# NBIOT.net
KiCad netlist of a schematic drawn in Altium Designer
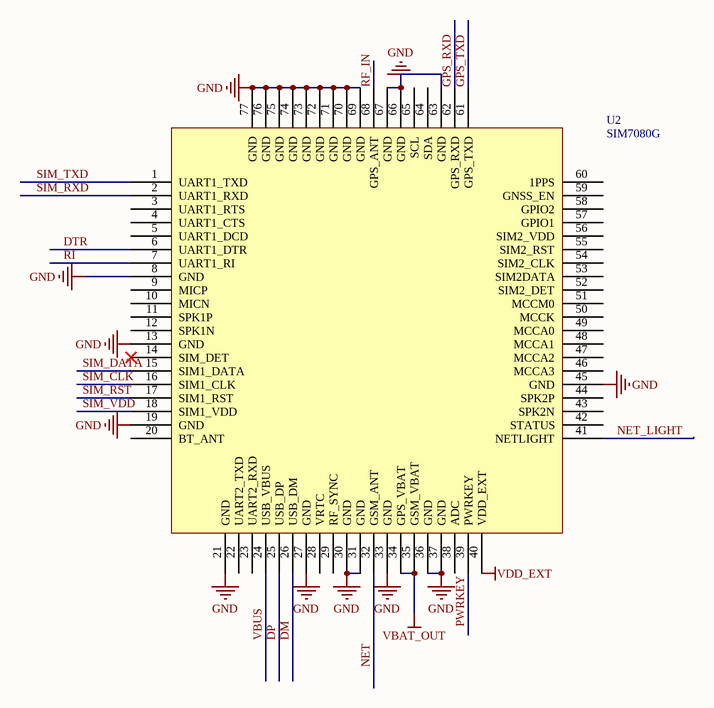
[diagram p0: NBIOT.SchDoc]

(export (version "E")
  (design (tool "Eeschema 10.0.6"))
  (components
    (comp (ref "U2")
      (value "SIM7080G")
      (footprint "SIM868")
      (libsource (lib "stm32") (part "SIM868E/SIM868"))
    )
  )
  (nets
    (net (code "1") (name "/DM") (class "Default")
      (node (ref "U2") (pin "26") (pinfunction "USB_DM_26") (pintype "passive"))
    )
    (net (code "2") (name "/DP") (class "Default")
      (node (ref "U2") (pin "25") (pinfunction "USB_DP_25") (pintype "passive"))
    )
    (net (code "3") (name "/DTR") (class "Default")
      (node (ref "U2") (pin "6") (pinfunction "UART1_DTR_6") (pintype "passive"))
    )
    (net (code "4") (name "/GPS_RXD") (class "Default")
      (node (ref "U2") (pin "62") (pinfunction "GPS_RXD_62") (pintype "passive"))
    )
    (net (code "5") (name "/GPS_TXD") (class "Default")
      (node (ref "U2") (pin "61") (pinfunction "GPS_TXD_61") (pintype "passive"))
    )
    (net (code "6") (name "/NET") (class "Default")
      (node (ref "U2") (pin "32") (pinfunction "GSM_ANT_32") (pintype "passive"))
    )
    (net (code "7") (name "/NET_LIGHT") (class "Default")
      (node (ref "U2") (pin "41") (pinfunction "NETLIGHT_41") (pintype "passive"))
    )
    (net (code "8") (name "/PWRKEY") (class "Default")
      (node (ref "U2") (pin "39") (pinfunction "PWRKEY_39") (pintype "passive"))
    )
    (net (code "9") (name "/RF_IN") (class "Default")
      (node (ref "U2") (pin "68") (pinfunction "GPS_ANT_68") (pintype "passive"))
    )
    (net (code "10") (name "/RI") (class "Default")
      (node (ref "U2") (pin "7") (pinfunction "UART1_RI_7") (pintype "passive"))
    )
    (net (code "11") (name "/SIM_CLK") (class "Default")
      (node (ref "U2") (pin "16") (pinfunction "SIM1_CLK_16") (pintype "passive"))
    )
    (net (code "12") (name "/SIM_DATA") (class "Default")
      (node (ref "U2") (pin "15") (pinfunction "SIM1_DATA_15") (pintype "passive"))
    )
    (net (code "13") (name "/SIM_RST") (class "Default")
      (node (ref "U2") (pin "17") (pinfunction "SIM1_RST_17") (pintype "passive"))
    )
    (net (code "14") (name "/SIM_RXD") (class "Default")
      (node (ref "U2") (pin "2") (pinfunction "UART1_RXD_2") (pintype "passive"))
    )
    (net (code "15") (name "/SIM_TXD") (class "Default")
      (node (ref "U2") (pin "1") (pinfunction "UART1_TXD_1") (pintype "passive"))
    )
    (net (code "16") (name "/SIM_VDD") (class "Default")
      (node (ref "U2") (pin "18") (pinfunction "SIM1_VDD_18") (pintype "passive"))
    )
    (net (code "17") (name "/VBUS") (class "Default")
      (node (ref "U2") (pin "24") (pinfunction "USB_VBUS_24") (pintype "passive"))
    )
    (net (code "18") (name "GND") (class "Default")
      (node (ref "U2") (pin "13") (pinfunction "GND_13") (pintype "passive"))
      (node (ref "U2") (pin "19") (pinfunction "GND_19") (pintype "passive"))
      (node (ref "U2") (pin "21") (pinfunction "GND_21") (pintype "passive"))
      (node (ref "U2") (pin "27") (pinfunction "GND_27") (pintype "passive"))
      (node (ref "U2") (pin "30") (pinfunction "GND_30") (pintype "passive"))
      (node (ref "U2") (pin "31") (pinfunction "GND_31") (pintype "passive"))
      (node (ref "U2") (pin "33") (pinfunction "GND_33") (pintype "passive"))
      (node (ref "U2") (pin "36") (pinfunction "GND_36") (pintype "passive"))
      (node (ref "U2") (pin "37") (pinfunction "GND_37") (pintype "passive"))
      (node (ref "U2") (pin "45") (pinfunction "GND_45") (pintype "passive"))
      (node (ref "U2") (pin "63") (pinfunction "GND_63") (pintype "passive"))
      (node (ref "U2") (pin "66") (pinfunction "GND_66") (pintype "passive"))
      (node (ref "U2") (pin "67") (pinfunction "GND_67") (pintype "passive"))
      (node (ref "U2") (pin "69") (pinfunction "GND_69") (pintype "passive"))
      (node (ref "U2") (pin "70") (pinfunction "GND_70") (pintype "passive"))
      (node (ref "U2") (pin "71") (pinfunction "GND_71") (pintype "passive"))
      (node (ref "U2") (pin "72") (pinfunction "GND_72") (pintype "passive"))
      (node (ref "U2") (pin "73") (pinfunction "GND_73") (pintype "passive"))
      (node (ref "U2") (pin "74") (pinfunction "GND_74") (pintype "passive"))
      (node (ref "U2") (pin "75") (pinfunction "GND_75") (pintype "passive"))
      (node (ref "U2") (pin "76") (pinfunction "GND_76") (pintype "passive"))
      (node (ref "U2") (pin "77") (pinfunction "GND_77") (pintype "passive"))
      (node (ref "U2") (pin "8") (pinfunction "GND_8") (pintype "passive"))
    )
    (net (code "19") (name "VBAT_OUT") (class "Default")
      (node (ref "U2") (pin "34") (pinfunction "GPS_VBAT_34") (pintype "passive"))
      (node (ref "U2") (pin "35") (pinfunction "GSM_VBAT_35") (pintype "passive"))
    )
    (net (code "20") (name "VDD_EXT") (class "Default")
      (node (ref "U2") (pin "40") (pinfunction "VDD_EXT_40") (pintype "passive"))
    )
    (net (code "21") (name "unconnected-(U2-1PPS-Pad60)") (class "Default")
      (node (ref "U2") (pin "60") (pinfunction "1PPS_60") (pintype "passive"))
    )
    (net (code "22") (name "unconnected-(U2-ADC-Pad38)") (class "Default")
      (node (ref "U2") (pin "38") (pinfunction "ADC_38") (pintype "passive"))
    )
    (net (code "23") (name "unconnected-(U2-BT_ANT-Pad20)") (class "Default")
      (node (ref "U2") (pin "20") (pinfunction "BT_ANT_20") (pintype "passive"))
    )
    (net (code "24") (name "unconnected-(U2-GNSS_EN-Pad59)") (class "Default")
      (node (ref "U2") (pin "59") (pinfunction "GNSS_EN_59") (pintype "passive"))
    )
    (net (code "25") (name "unconnected-(U2-GPIO1-Pad57)") (class "Default")
      (node (ref "U2") (pin "57") (pinfunction "GPIO1_57") (pintype "passive"))
    )
    (net (code "26") (name "unconnected-(U2-GPIO2-Pad58)") (class "Default")
      (node (ref "U2") (pin "58") (pinfunction "GPIO2_58") (pintype "passive"))
    )
    (net (code "27") (name "unconnected-(U2-MCCA0-Pad49)") (class "Default")
      (node (ref "U2") (pin "49") (pinfunction "MCCA0_49") (pintype "passive"))
    )
    (net (code "28") (name "unconnected-(U2-MCCA1-Pad48)") (class "Default")
      (node (ref "U2") (pin "48") (pinfunction "MCCA1_48") (pintype "passive"))
    )
    (net (code "29") (name "unconnected-(U2-MCCA2-Pad47)") (class "Default")
      (node (ref "U2") (pin "47") (pinfunction "MCCA2_47") (pintype "passive"))
    )
    (net (code "30") (name "unconnected-(U2-MCCA3-Pad46)") (class "Default")
      (node (ref "U2") (pin "46") (pinfunction "MCCA3_46") (pintype "passive"))
    )
    (net (code "31") (name "unconnected-(U2-MCCK-Pad50)") (class "Default")
      (node (ref "U2") (pin "50") (pinfunction "MCCK_50") (pintype "passive"))
    )
    (net (code "32") (name "unconnected-(U2-MCCM0-Pad51)") (class "Default")
      (node (ref "U2") (pin "51") (pinfunction "MCCM0_51") (pintype "passive"))
    )
    (net (code "33") (name "unconnected-(U2-MICN-Pad10)") (class "Default")
      (node (ref "U2") (pin "10") (pinfunction "MICN_10") (pintype "passive"))
    )
    (net (code "34") (name "unconnected-(U2-MICP-Pad9)") (class "Default")
      (node (ref "U2") (pin "9") (pinfunction "MICP_9") (pintype "passive"))
    )
    (net (code "35") (name "unconnected-(U2-RF_SYNC-Pad29)") (class "Default")
      (node (ref "U2") (pin "29") (pinfunction "RF_SYNC_29") (pintype "passive"))
    )
    (net (code "36") (name "unconnected-(U2-SCL-Pad65)") (class "Default")
      (node (ref "U2") (pin "65") (pinfunction "SCL_65") (pintype "passive"))
    )
    (net (code "37") (name "unconnected-(U2-SDA-Pad64)") (class "Default")
      (node (ref "U2") (pin "64") (pinfunction "SDA_64") (pintype "passive"))
    )
    (net (code "38") (name "unconnected-(U2-SIM2DATA-Pad53)") (class "Default")
      (node (ref "U2") (pin "53") (pinfunction "SIM2DATA_53") (pintype "passive"))
    )
    (net (code "39") (name "unconnected-(U2-SIM2_CLK-Pad54)") (class "Default")
      (node (ref "U2") (pin "54") (pinfunction "SIM2_CLK_54") (pintype "passive"))
    )
    (net (code "40") (name "unconnected-(U2-SIM2_DET-Pad52)") (class "Default")
      (node (ref "U2") (pin "52") (pinfunction "SIM2_DET_52") (pintype "passive"))
    )
    (net (code "41") (name "unconnected-(U2-SIM2_RST-Pad55)") (class "Default")
      (node (ref "U2") (pin "55") (pinfunction "SIM2_RST_55") (pintype "passive"))
    )
    (net (code "42") (name "unconnected-(U2-SIM2_VDD-Pad56)") (class "Default")
      (node (ref "U2") (pin "56") (pinfunction "SIM2_VDD_56") (pintype "passive"))
    )
    (net (code "43") (name "unconnected-(U2-SIM_DET-Pad14)") (class "Default")
      (node (ref "U2") (pin "14") (pinfunction "SIM_DET_14") (pintype "passive+no_connect"))
    )
    (net (code "44") (name "unconnected-(U2-SPK1N-Pad12)") (class "Default")
      (node (ref "U2") (pin "12") (pinfunction "SPK1N_12") (pintype "passive"))
    )
    (net (code "45") (name "unconnected-(U2-SPK1P-Pad11)") (class "Default")
      (node (ref "U2") (pin "11") (pinfunction "SPK1P_11") (pintype "passive"))
    )
    (net (code "46") (name "unconnected-(U2-SPK2N-Pad43)") (class "Default")
      (node (ref "U2") (pin "43") (pinfunction "SPK2N_43") (pintype "passive"))
    )
    (net (code "47") (name "unconnected-(U2-SPK2P-Pad44)") (class "Default")
      (node (ref "U2") (pin "44") (pinfunction "SPK2P_44") (pintype "passive"))
    )
    (net (code "48") (name "unconnected-(U2-STATUS-Pad42)") (class "Default")
      (node (ref "U2") (pin "42") (pinfunction "STATUS_42") (pintype "passive"))
    )
    (net (code "49") (name "unconnected-(U2-UART1_CTS-Pad4)") (class "Default")
      (node (ref "U2") (pin "4") (pinfunction "UART1_CTS_4") (pintype "passive"))
    )
    (net (code "50") (name "unconnected-(U2-UART1_DCD-Pad5)") (class "Default")
      (node (ref "U2") (pin "5") (pinfunction "UART1_DCD_5") (pintype "passive"))
    )
    (net (code "51") (name "unconnected-(U2-UART1_RTS-Pad3)") (class "Default")
      (node (ref "U2") (pin "3") (pinfunction "UART1_RTS_3") (pintype "passive"))
    )
    (net (code "52") (name "unconnected-(U2-UART2_RXD-Pad23)") (class "Default")
      (node (ref "U2") (pin "23") (pinfunction "UART2_RXD_23") (pintype "passive"))
    )
    (net (code "53") (name "unconnected-(U2-UART2_TXD-Pad22)") (class "Default")
      (node (ref "U2") (pin "22") (pinfunction "UART2_TXD_22") (pintype "passive"))
    )
    (net (code "54") (name "unconnected-(U2-VRTC-Pad28)") (class "Default")
      (node (ref "U2") (pin "28") (pinfunction "VRTC_28") (pintype "passive"))
    )
  )
)
